# injector.net
KiCad netlist of a schematic drawn in EAGLE
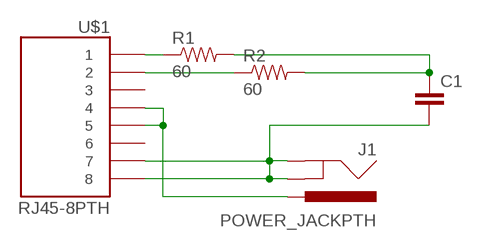
[diagram p0: schematic, sheet 1]

(export (version "E")
  (design (tool "Eeschema 10.0.6"))
  (components
    (comp (ref "C1")
      (value "CAP0603-CAP")
      (footprint "eagle-import:0603-CAP")
      (libsource (lib "eagle-import") (part "CAP0603-CAP"))
    )
    (comp (ref "J1")
      (value "POWER_JACKPTH")
      (footprint "eagle-import:POWER_JACK_PTH")
      (libsource (lib "eagle-import") (part "POWER_JACKPTH"))
    )
    (comp (ref "R1")
      (value "60")
      (footprint "eagle-import:0603-RES")
      (libsource (lib "eagle-import") (part "RESISTOR0603-RES"))
    )
    (comp (ref "R2")
      (value "60")
      (footprint "eagle-import:0603-RES")
      (libsource (lib "eagle-import") (part "RESISTOR0603-RES"))
    )
    (comp (ref "U$1")
      (value "RJ45-8PTH")
      (footprint "eagle-import:RJ45-8")
      (libsource (lib "eagle-import") (part "RJ45-8PTH"))
    )
  )
  (nets
    (net (code "1") (name "Net-(C1-Pad1)") (class "Default")
      (node (ref "C1") (pin "1") (pinfunction "1_1") (pintype "passive"))
      (node (ref "R1") (pin "2") (pinfunction "2_2") (pintype "passive"))
      (node (ref "R2") (pin "2") (pinfunction "2_2") (pintype "passive"))
    )
    (net (code "2") (name "Net-(C1-Pad2)") (class "Default")
      (node (ref "C1") (pin "2") (pinfunction "2_2") (pintype "passive"))
      (node (ref "J1") (pin "GND") (pinfunction "GND_GND") (pintype "bidirectional"))
      (node (ref "J1") (pin "GNDBREAK") (pinfunction "GNDBREAK_GNDBREAK") (pintype "bidirectional"))
      (node (ref "U$1") (pin "7") (pinfunction "7_7") (pintype "bidirectional"))
      (node (ref "U$1") (pin "8") (pinfunction "8_8") (pintype "bidirectional"))
    )
    (net (code "3") (name "Net-(J1-PadPWR)") (class "Default")
      (node (ref "J1") (pin "PWR") (pinfunction "PWR_PWR") (pintype "bidirectional"))
      (node (ref "U$1") (pin "4") (pinfunction "4_4") (pintype "bidirectional"))
      (node (ref "U$1") (pin "5") (pinfunction "5_5") (pintype "bidirectional"))
    )
    (net (code "4") (name "Net-(R1-Pad1)") (class "Default")
      (node (ref "R1") (pin "1") (pinfunction "1_1") (pintype "passive"))
      (node (ref "U$1") (pin "1") (pinfunction "1_1") (pintype "bidirectional"))
    )
    (net (code "5") (name "Net-(R2-Pad1)") (class "Default")
      (node (ref "R2") (pin "1") (pinfunction "1_1") (pintype "passive"))
      (node (ref "U$1") (pin "2") (pinfunction "2_2") (pintype "bidirectional"))
    )
    (net (code "6") (name "unconnected-(U$1-Pad3)") (class "Default")
      (node (ref "U$1") (pin "3") (pinfunction "3_3") (pintype "bidirectional"))
    )
    (net (code "7") (name "unconnected-(U$1-Pad6)") (class "Default")
      (node (ref "U$1") (pin "6") (pinfunction "6_6") (pintype "bidirectional"))
    )
  )
)
